# RCS_Battery_Pack_v2.net
KiCad netlist of a schematic drawn in EAGLE
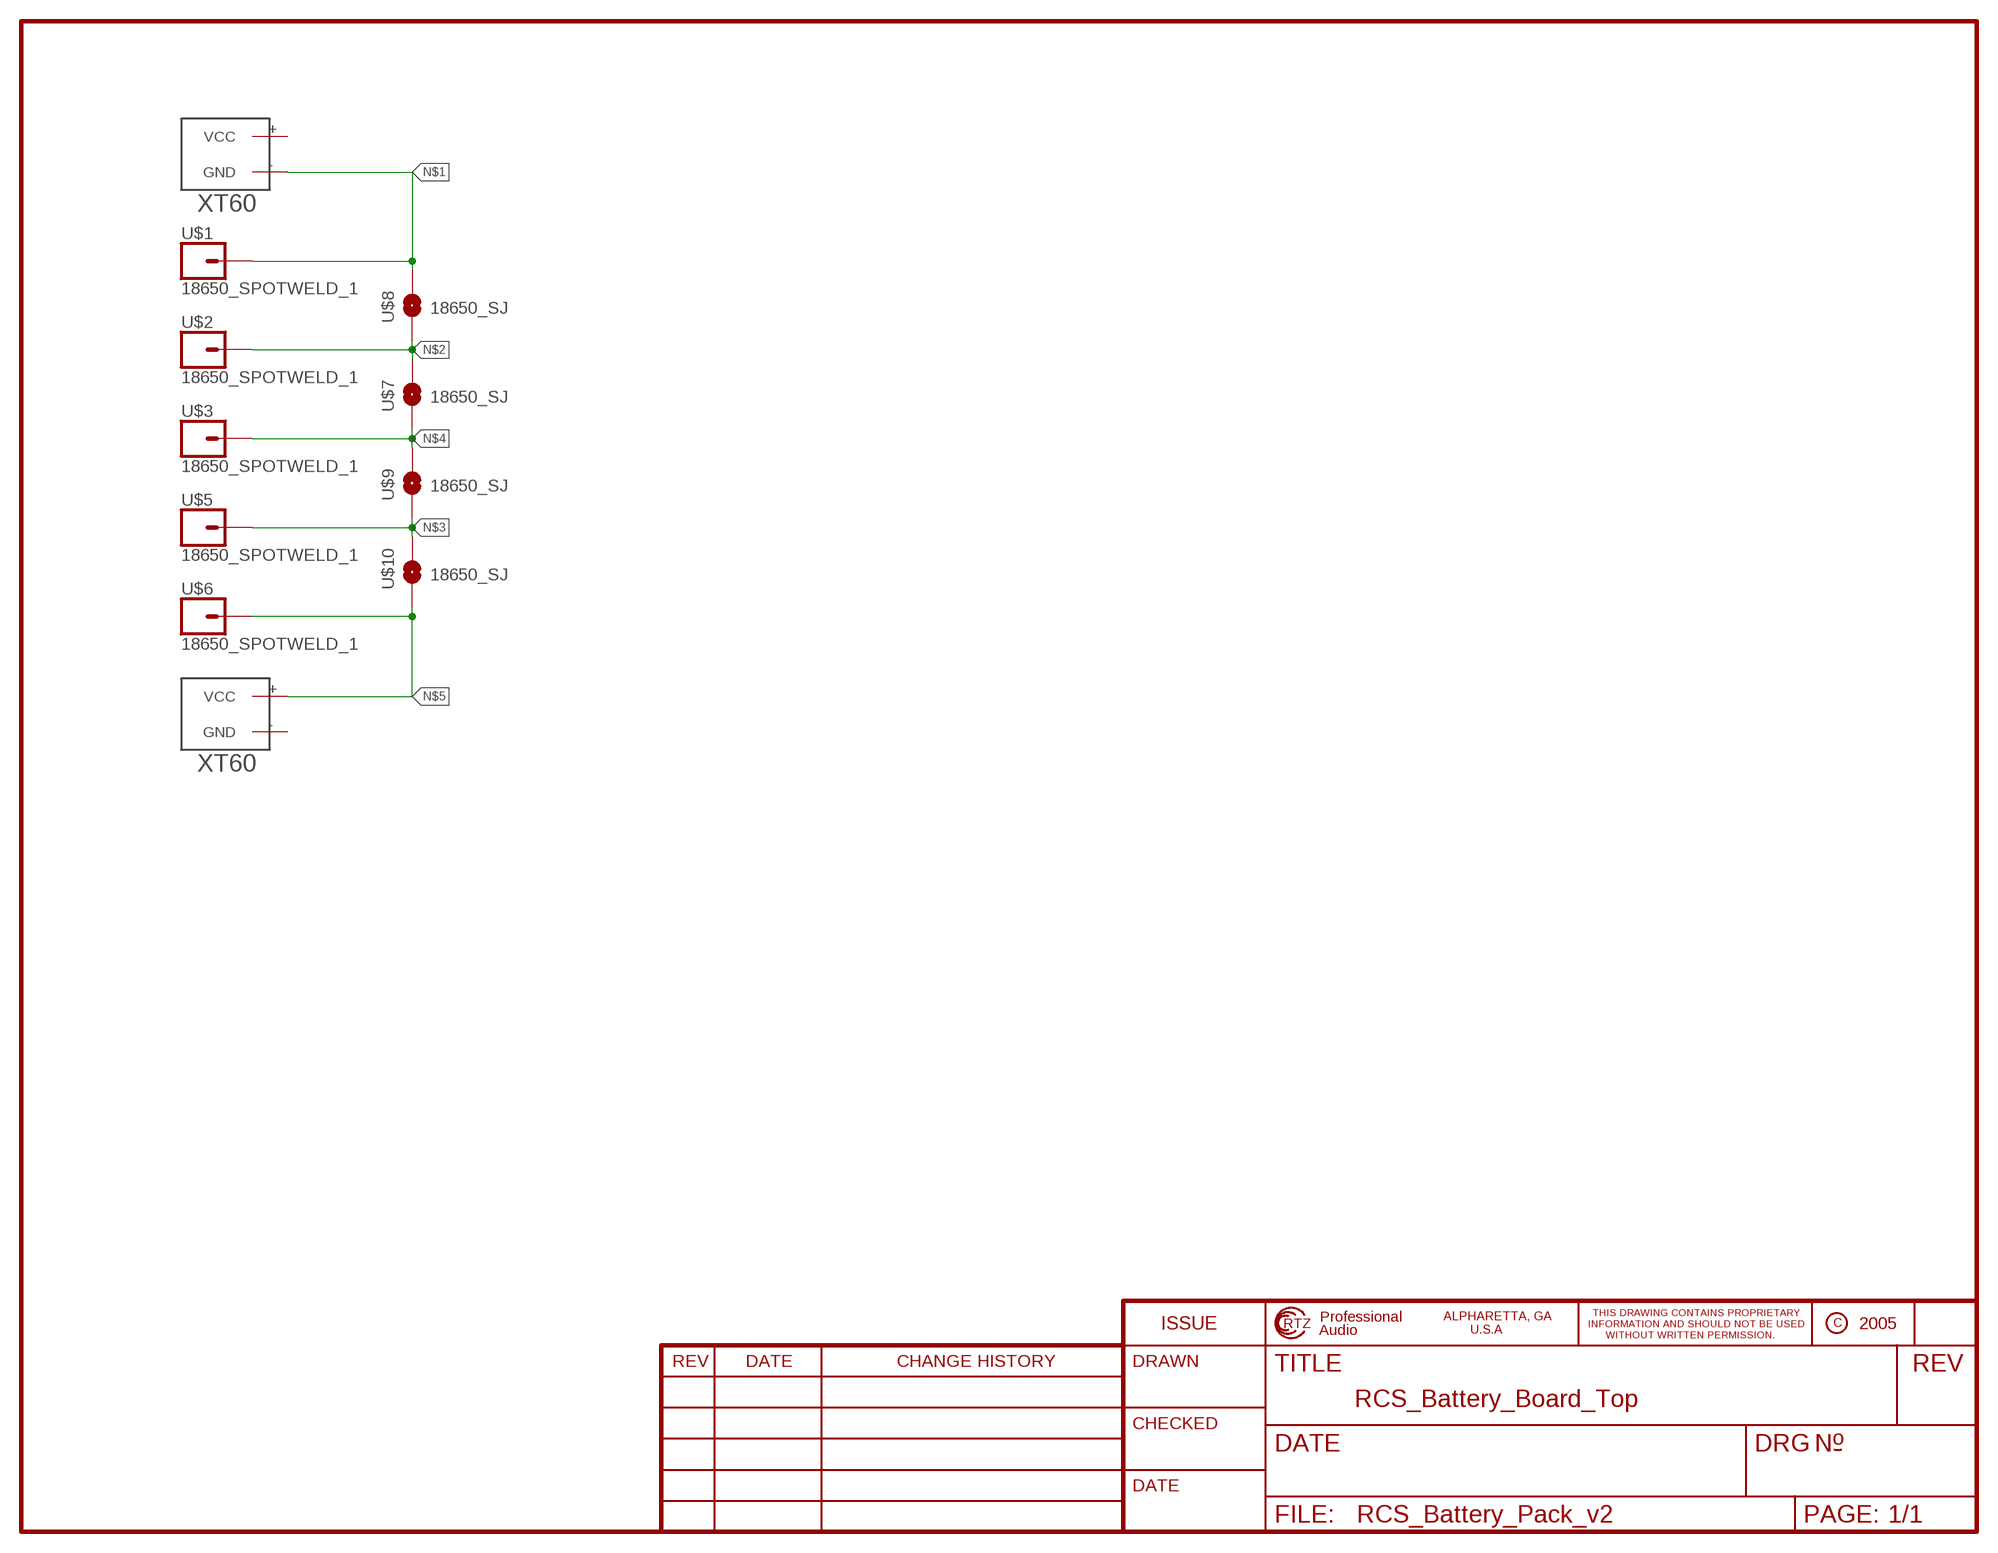
[diagram p0: schematic, sheet 1]

(export (version "E")
  (design (tool "Eeschema 10.0.6"))
  (components
    (comp (ref "U$1")
      (value "18650_SPOTWELD_1")
      (footprint "eagle-import:18650_SPOTWELD_1")
      (libsource (lib "eagle-import") (part "18650_SPOTWELD_1"))
    )
    (comp (ref "U$2")
      (value "18650_SPOTWELD_1")
      (footprint "eagle-import:18650_SPOTWELD_1")
      (libsource (lib "eagle-import") (part "18650_SPOTWELD_1"))
    )
    (comp (ref "U$3")
      (value "18650_SPOTWELD_1")
      (footprint "eagle-import:18650_SPOTWELD_1")
      (libsource (lib "eagle-import") (part "18650_SPOTWELD_1"))
    )
    (comp (ref "U$4")
      (value "XT60")
      (footprint "eagle-import:XT60")
      (libsource (lib "eagle-import") (part "XT60"))
    )
    (comp (ref "U$5")
      (value "18650_SPOTWELD_1")
      (footprint "eagle-import:18650_SPOTWELD_1")
      (libsource (lib "eagle-import") (part "18650_SPOTWELD_1"))
    )
    (comp (ref "U$6")
      (value "18650_SPOTWELD_1")
      (footprint "eagle-import:18650_SPOTWELD_1")
      (libsource (lib "eagle-import") (part "18650_SPOTWELD_1"))
    )
    (comp (ref "U$7")
      (value "18650_SJ")
      (footprint "eagle-import:SJ_2S-NO")
      (libsource (lib "eagle-import") (part "18650_SJ"))
    )
    (comp (ref "U$8")
      (value "18650_SJ")
      (footprint "eagle-import:SJ_2S-NO")
      (libsource (lib "eagle-import") (part "18650_SJ"))
    )
    (comp (ref "U$9")
      (value "18650_SJ")
      (footprint "eagle-import:SJ_2S-NO")
      (libsource (lib "eagle-import") (part "18650_SJ"))
    )
    (comp (ref "U$10")
      (value "18650_SJ")
      (footprint "eagle-import:SJ_2S-NO")
      (libsource (lib "eagle-import") (part "18650_SJ"))
    )
    (comp (ref "U$11")
      (value "XT60")
      (footprint "eagle-import:XT60")
      (libsource (lib "eagle-import") (part "XT60"))
    )
  )
  (nets
    (net (code "1") (name "N$1") (class "Default")
      (node (ref "U$1") (pin "1") (pinfunction "1_1") (pintype "passive"))
      (node (ref "U$4") (pin "-") (pinfunction "GND_-") (pintype "bidirectional"))
      (node (ref "U$8") (pin "2") (pinfunction "2_2") (pintype "passive"))
    )
    (net (code "2") (name "N$2") (class "Default")
      (node (ref "U$2") (pin "1") (pinfunction "1_1") (pintype "passive"))
      (node (ref "U$7") (pin "2") (pinfunction "2_2") (pintype "passive"))
      (node (ref "U$8") (pin "1") (pinfunction "1_1") (pintype "passive"))
    )
    (net (code "3") (name "N$3") (class "Default")
      (node (ref "U$10") (pin "2") (pinfunction "2_2") (pintype "passive"))
      (node (ref "U$5") (pin "1") (pinfunction "1_1") (pintype "passive"))
      (node (ref "U$9") (pin "1") (pinfunction "1_1") (pintype "passive"))
    )
    (net (code "4") (name "N$4") (class "Default")
      (node (ref "U$3") (pin "1") (pinfunction "1_1") (pintype "passive"))
      (node (ref "U$7") (pin "1") (pinfunction "1_1") (pintype "passive"))
      (node (ref "U$9") (pin "2") (pinfunction "2_2") (pintype "passive"))
    )
    (net (code "5") (name "N$5") (class "Default")
      (node (ref "U$10") (pin "1") (pinfunction "1_1") (pintype "passive"))
      (node (ref "U$11") (pin "+") (pinfunction "VCC_+") (pintype "bidirectional"))
      (node (ref "U$6") (pin "1") (pinfunction "1_1") (pintype "passive"))
    )
    (net (code "6") (name "unconnected-(U$4-VCC-Pad+)") (class "Default")
      (node (ref "U$4") (pin "+") (pinfunction "VCC_+") (pintype "bidirectional"))
    )
    (net (code "7") (name "unconnected-(U$11-GND-Pad-)") (class "Default")
      (node (ref "U$11") (pin "-") (pinfunction "GND_-") (pintype "bidirectional"))
    )
  )
)
